# multi-pcb-analog.net
KiCad netlist of a schematic drawn in EAGLE
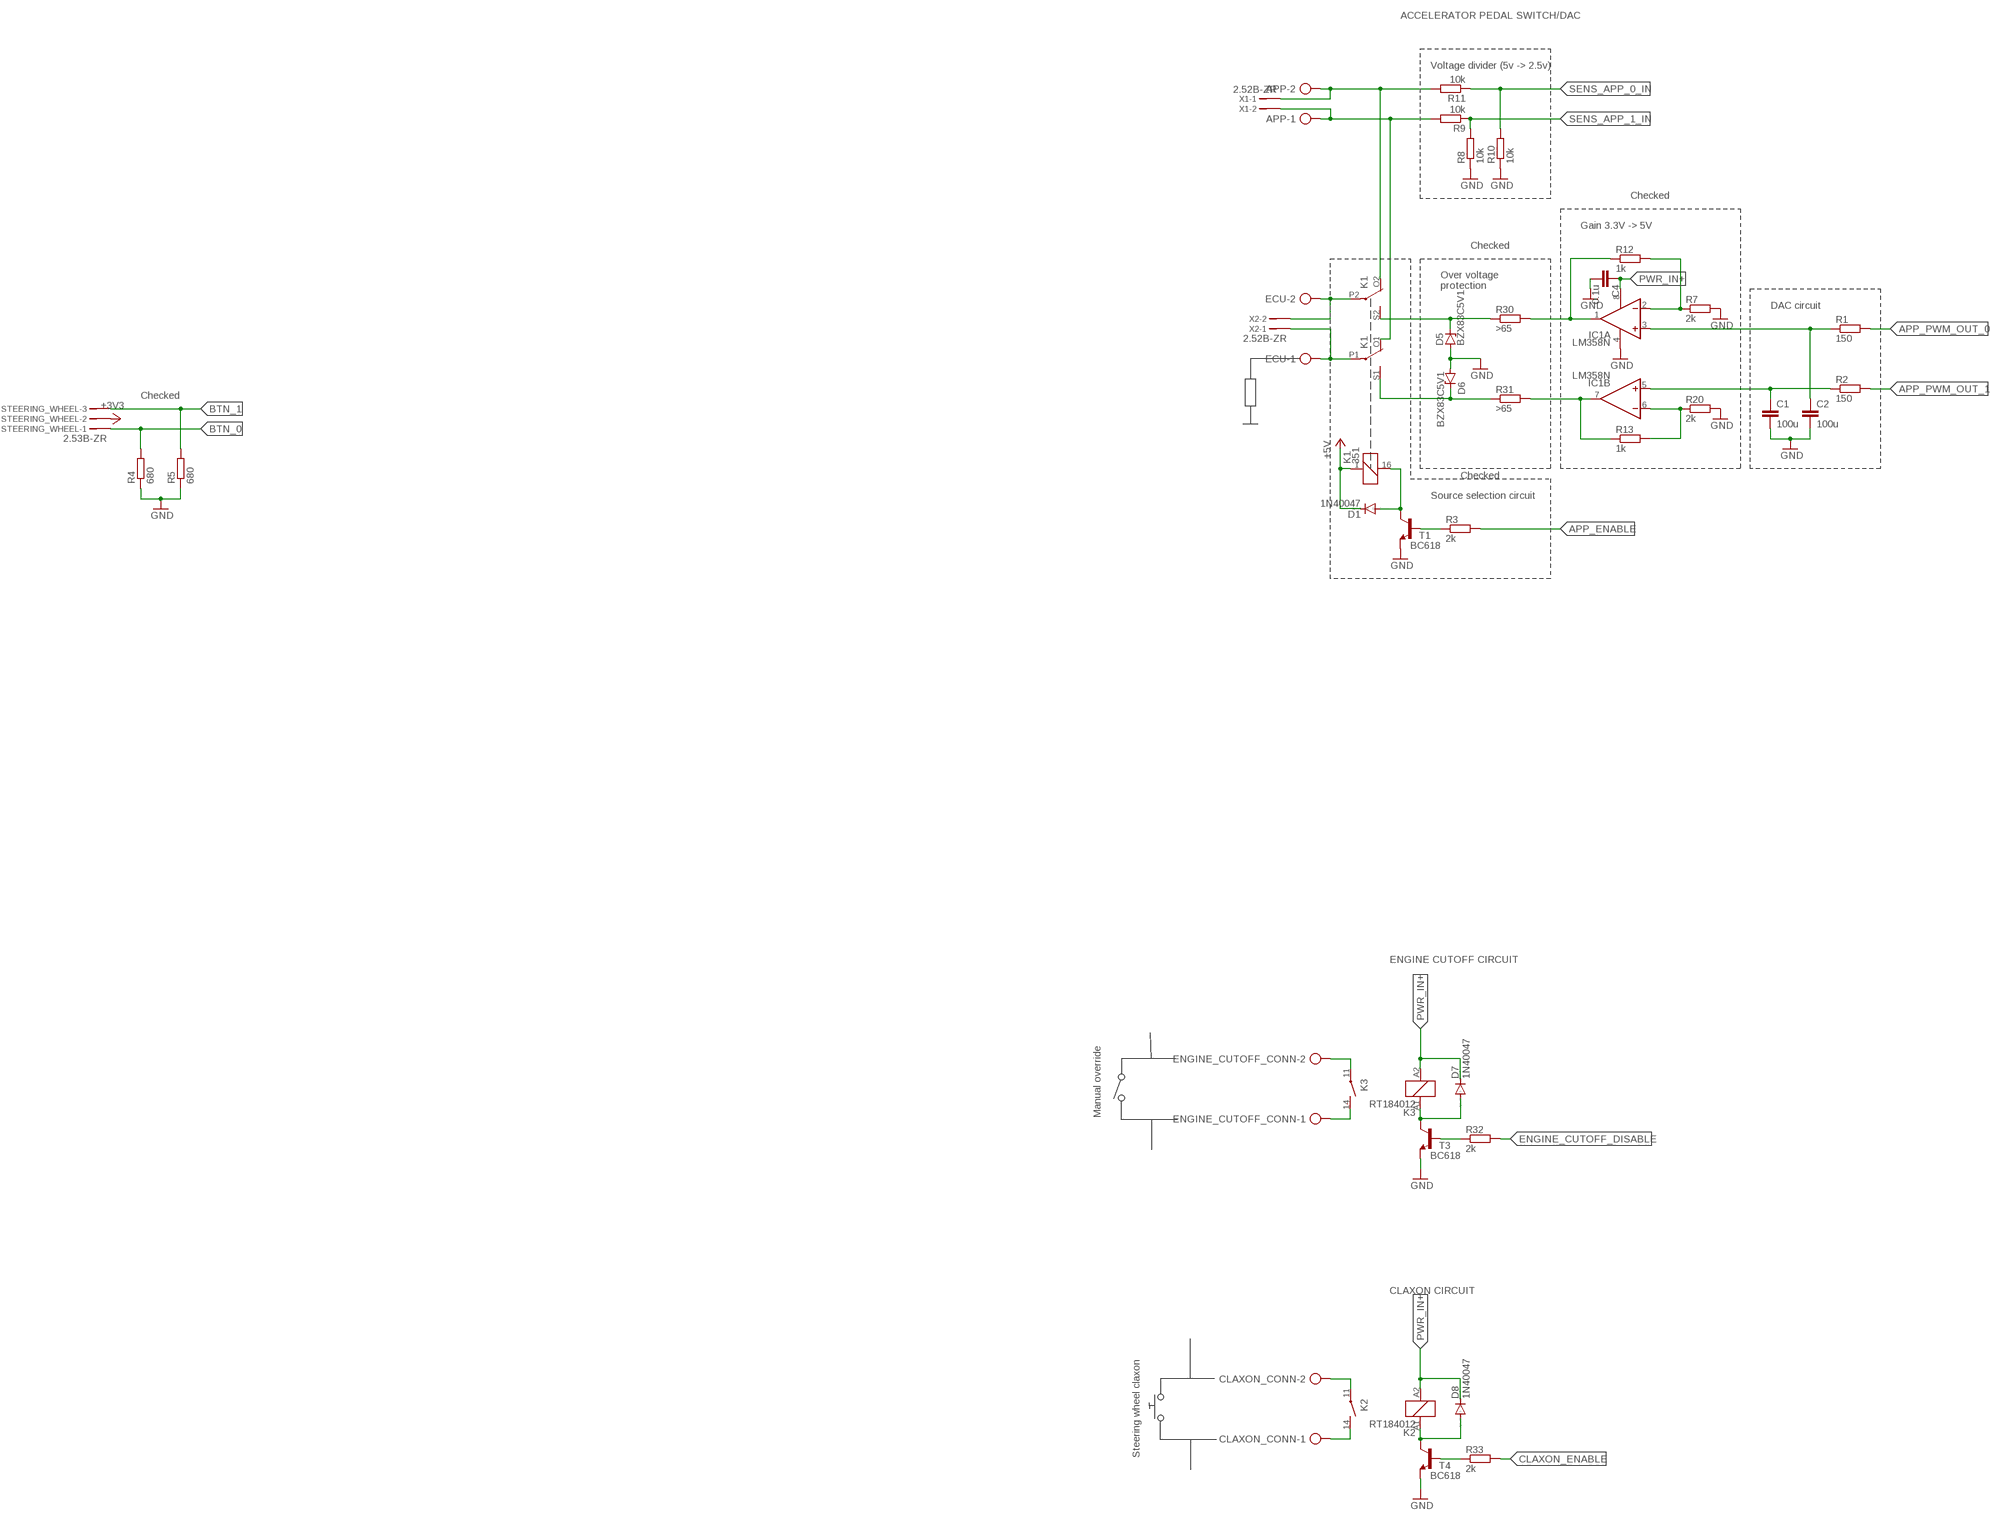
[diagram p0: schematic, sheet 1]

(export (version "E")
  (design (tool "Eeschema 10.0.6"))
  (components
    (comp (ref "APP")
      (value "AK300/2")
      (footprint "eagle-import:AK300_2")
      (libsource (lib "eagle-import") (part "AK300/2"))
    )
    (comp (ref "C1")
      (value "100u")
      (footprint "eagle-import:C025-050X050")
      (libsource (lib "eagle-import") (part "C-EU025-050X050"))
    )
    (comp (ref "C2")
      (value "100u")
      (footprint "eagle-import:C025-050X050")
      (libsource (lib "eagle-import") (part "C-EU025-050X050"))
    )
    (comp (ref "C4")
      (value "0.1u")
      (footprint "eagle-import:C025-050X050")
      (libsource (lib "eagle-import") (part "C-EU025-050X050"))
    )
    (comp (ref "CLAXON_CONN")
      (value "AK300/2")
      (footprint "eagle-import:AK300_2")
      (libsource (lib "eagle-import") (part "AK300/2"))
    )
    (comp (ref "D1")
      (value "1N40047")
      (footprint "eagle-import:DO41-7.6")
      (libsource (lib "eagle-import") (part "1N40047"))
    )
    (comp (ref "D5")
      (value "BZX83C5V1")
      (footprint "eagle-import:DO41Z7.6")
      (libsource (lib "eagle-import") (part "BZX857"))
    )
    (comp (ref "D6")
      (value "BZX83C5V1")
      (footprint "eagle-import:DO41Z7.6")
      (libsource (lib "eagle-import") (part "BZX857"))
    )
    (comp (ref "D7")
      (value "1N40047")
      (footprint "eagle-import:DO41-7.6")
      (libsource (lib "eagle-import") (part "1N40047"))
    )
    (comp (ref "D8")
      (value "1N40047")
      (footprint "eagle-import:DO41-7.6")
      (libsource (lib "eagle-import") (part "1N40047"))
    )
    (comp (ref "ECU")
      (value "AK300/2")
      (footprint "eagle-import:AK300_2")
      (libsource (lib "eagle-import") (part "AK300/2"))
    )
    (comp (ref "ENGINE_CUTOFF_CONN")
      (value "AK300/2")
      (footprint "eagle-import:AK300_2")
      (libsource (lib "eagle-import") (part "AK300/2"))
    )
    (comp (ref "IC1")
      (value "LM358N")
      (footprint "eagle-import:DIL08")
      (libsource (lib "eagle-import") (part "LM358N"))
    )
    (comp (ref "K1")
      (value "351")
      (footprint "eagle-import:351")
      (libsource (lib "eagle-import") (part "351"))
    )
    (comp (ref "K2")
      (value "RT184012")
      (footprint "eagle-import:RT-N_O12A3.5")
      (fields (field (name "MF") "TYCO ELECTRONICS"))
      (libsource (lib "eagle-import") (part "RT?184012"))
    )
    (comp (ref "K3")
      (value "RT184012")
      (footprint "eagle-import:RT-N_O12A3.5")
      (fields (field (name "MF") "TYCO ELECTRONICS"))
      (libsource (lib "eagle-import") (part "RT?184012"))
    )
    (comp (ref "R1")
      (value "150")
      (footprint "eagle-import:0309_10")
      (libsource (lib "eagle-import") (part "R-EU_0309/10"))
    )
    (comp (ref "R2")
      (value "150")
      (footprint "eagle-import:0309_10")
      (libsource (lib "eagle-import") (part "R-EU_0309/10"))
    )
    (comp (ref "R3")
      (value "2k")
      (footprint "eagle-import:0207_7")
      (libsource (lib "eagle-import") (part "R-EU_0207/7"))
    )
    (comp (ref "R4")
      (value "680")
      (footprint "eagle-import:0207_7")
      (libsource (lib "eagle-import") (part "R-EU_0207/7"))
    )
    (comp (ref "R5")
      (value "680")
      (footprint "eagle-import:0207_7")
      (libsource (lib "eagle-import") (part "R-EU_0207/7"))
    )
    (comp (ref "R7")
      (value "2k")
      (footprint "eagle-import:0207_7")
      (libsource (lib "eagle-import") (part "R-EU_0207/7"))
    )
    (comp (ref "R8")
      (value "10k")
      (footprint "eagle-import:0207_7")
      (libsource (lib "eagle-import") (part "R-EU_0207/7"))
    )
    (comp (ref "R9")
      (value "10k")
      (footprint "eagle-import:0309_10")
      (libsource (lib "eagle-import") (part "R-EU_0309/10"))
    )
    (comp (ref "R10")
      (value "10k")
      (footprint "eagle-import:0207_7")
      (libsource (lib "eagle-import") (part "R-EU_0207/7"))
    )
    (comp (ref "R11")
      (value "10k")
      (footprint "eagle-import:0309_10")
      (libsource (lib "eagle-import") (part "R-EU_0309/10"))
    )
    (comp (ref "R12")
      (value "1k")
      (footprint "eagle-import:0207_7")
      (libsource (lib "eagle-import") (part "R-EU_0207/7"))
    )
    (comp (ref "R13")
      (value "1k")
      (footprint "eagle-import:0207_7")
      (libsource (lib "eagle-import") (part "R-EU_0207/7"))
    )
    (comp (ref "R20")
      (value "2k")
      (footprint "eagle-import:0207_7")
      (libsource (lib "eagle-import") (part "R-EU_0207/7"))
    )
    (comp (ref "R30")
      (value ">65")
      (footprint "eagle-import:0207_7")
      (libsource (lib "eagle-import") (part "R-EU_0207/7"))
    )
    (comp (ref "R31")
      (value ">65")
      (footprint "eagle-import:0207_7")
      (libsource (lib "eagle-import") (part "R-EU_0207/7"))
    )
    (comp (ref "R32")
      (value "2k")
      (footprint "eagle-import:0309_10")
      (libsource (lib "eagle-import") (part "R-EU_0309/10"))
    )
    (comp (ref "R33")
      (value "2k")
      (footprint "eagle-import:0309_10")
      (libsource (lib "eagle-import") (part "R-EU_0309/10"))
    )
    (comp (ref "STEERING_WHEEL")
      (value "2.53B-ZR")
      (footprint "eagle-import:B3B-ZR2.5")
      (libsource (lib "eagle-import") (part "?3B-ZR2.5"))
    )
    (comp (ref "T1")
      (value "BC618")
      (footprint "eagle-import:TO92-EBC")
      (libsource (lib "eagle-import") (part "BC618"))
    )
    (comp (ref "T3")
      (value "BC618")
      (footprint "eagle-import:TO92-EBC")
      (libsource (lib "eagle-import") (part "BC618"))
    )
    (comp (ref "T4")
      (value "BC618")
      (footprint "eagle-import:TO92-EBC")
      (libsource (lib "eagle-import") (part "BC618"))
    )
    (comp (ref "X1")
      (value "2.52B-ZR")
      (footprint "eagle-import:B2B-ZR2.5")
      (libsource (lib "eagle-import") (part "?2B-ZR2.5"))
    )
    (comp (ref "X2")
      (value "2.52B-ZR")
      (footprint "eagle-import:B2B-ZR2.5")
      (libsource (lib "eagle-import") (part "?2B-ZR2.5"))
    )
  )
  (nets
    (net (code "1") (name "+3V3") (class "Default")
      (node (ref "STEERING_WHEEL") (pin "2") (pinfunction "1_2") (pintype "passive"))
    )
    (net (code "2") (name "+5V") (class "Default")
      (node (ref "D1") (pin "C") (pinfunction "C_C") (pintype "passive"))
      (node (ref "K1") (pin "1") (pinfunction "1_1") (pintype "passive"))
    )
    (net (code "3") (name "APP_ENABLE") (class "Default")
      (node (ref "R3") (pin "2") (pinfunction "2_2") (pintype "passive"))
    )
    (net (code "4") (name "APP_PWM_OUT_0") (class "Default")
      (node (ref "R1") (pin "2") (pinfunction "2_2") (pintype "passive"))
    )
    (net (code "5") (name "APP_PWM_OUT_1") (class "Default")
      (node (ref "R2") (pin "2") (pinfunction "2_2") (pintype "passive"))
    )
    (net (code "6") (name "BTN_0") (class "Default")
      (node (ref "R4") (pin "2") (pinfunction "2_2") (pintype "passive"))
      (node (ref "STEERING_WHEEL") (pin "1") (pinfunction "1_1") (pintype "passive"))
    )
    (net (code "7") (name "BTN_1") (class "Default")
      (node (ref "R5") (pin "2") (pinfunction "2_2") (pintype "passive"))
      (node (ref "STEERING_WHEEL") (pin "3") (pinfunction "1_3") (pintype "passive"))
    )
    (net (code "8") (name "CLAXON_ENABLE") (class "Default")
      (node (ref "R33") (pin "2") (pinfunction "2_2") (pintype "passive"))
    )
    (net (code "9") (name "ENGINE_CUTOFF_DISABLE") (class "Default")
      (node (ref "R32") (pin "2") (pinfunction "2_2") (pintype "passive"))
    )
    (net (code "10") (name "GND") (class "Default")
      (node (ref "C1") (pin "2") (pinfunction "2_2") (pintype "passive"))
      (node (ref "C2") (pin "2") (pinfunction "2_2") (pintype "passive"))
      (node (ref "C4") (pin "2") (pinfunction "2_2") (pintype "passive"))
      (node (ref "D5") (pin "A") (pinfunction "A_A") (pintype "passive"))
      (node (ref "D6") (pin "A") (pinfunction "A_A") (pintype "passive"))
      (node (ref "IC1") (pin "4") (pinfunction "V-_4") (pintype "power_in"))
      (node (ref "R10") (pin "1") (pinfunction "1_1") (pintype "passive"))
      (node (ref "R20") (pin "2") (pinfunction "2_2") (pintype "passive"))
      (node (ref "R4") (pin "1") (pinfunction "1_1") (pintype "passive"))
      (node (ref "R5") (pin "1") (pinfunction "1_1") (pintype "passive"))
      (node (ref "R7") (pin "2") (pinfunction "2_2") (pintype "passive"))
      (node (ref "R8") (pin "1") (pinfunction "1_1") (pintype "passive"))
      (node (ref "T1") (pin "E") (pinfunction "E_E") (pintype "passive"))
      (node (ref "T3") (pin "E") (pinfunction "E_E") (pintype "passive"))
      (node (ref "T4") (pin "E") (pinfunction "E_E") (pintype "passive"))
    )
    (net (code "11") (name "Net-(APPA-KL)") (class "Default")
      (node (ref "APP") (pin "1") (pinfunction "KL_1") (pintype "passive"))
      (node (ref "K1") (pin "O1") (pinfunction "O_O1") (pintype "passive"))
      (node (ref "R9") (pin "2") (pinfunction "2_2") (pintype "passive"))
      (node (ref "X1") (pin "2") (pinfunction "1_2") (pintype "passive"))
    )
    (net (code "12") (name "Net-(APPB-KL)") (class "Default")
      (node (ref "APP") (pin "2") (pinfunction "KL_2") (pintype "passive"))
      (node (ref "K1") (pin "O2") (pinfunction "O_O2") (pintype "passive"))
      (node (ref "R11") (pin "2") (pinfunction "2_2") (pintype "passive"))
      (node (ref "X1") (pin "1") (pinfunction "1_1") (pintype "passive"))
    )
    (net (code "13") (name "Net-(CLAXON_CONNA-KL)") (class "Default")
      (node (ref "CLAXON_CONN") (pin "1") (pinfunction "KL_1") (pintype "passive"))
      (node (ref "K2") (pin "14") (pinfunction "S_14") (pintype "passive"))
    )
    (net (code "14") (name "Net-(CLAXON_CONNB-KL)") (class "Default")
      (node (ref "CLAXON_CONN") (pin "2") (pinfunction "KL_2") (pintype "passive"))
      (node (ref "K2") (pin "11") (pinfunction "P_11") (pintype "passive"))
    )
    (net (code "15") (name "Net-(ECUA-KL)") (class "Default")
      (node (ref "ECU") (pin "1") (pinfunction "KL_1") (pintype "passive"))
      (node (ref "K1") (pin "P1") (pinfunction "P_P1") (pintype "passive"))
      (node (ref "X2") (pin "1") (pinfunction "1_1") (pintype "passive"))
    )
    (net (code "16") (name "Net-(ECUB-KL)") (class "Default")
      (node (ref "ECU") (pin "2") (pinfunction "KL_2") (pintype "passive"))
      (node (ref "K1") (pin "P2") (pinfunction "P_P2") (pintype "passive"))
      (node (ref "X2") (pin "2") (pinfunction "1_2") (pintype "passive"))
    )
    (net (code "17") (name "Net-(ENGINE_CUTOFF_CONNA-KL)") (class "Default")
      (node (ref "ENGINE_CUTOFF_CONN") (pin "1") (pinfunction "KL_1") (pintype "passive"))
      (node (ref "K3") (pin "14") (pinfunction "S_14") (pintype "passive"))
    )
    (net (code "18") (name "Net-(ENGINE_CUTOFF_CONNB-KL)") (class "Default")
      (node (ref "ENGINE_CUTOFF_CONN") (pin "2") (pinfunction "KL_2") (pintype "passive"))
      (node (ref "K3") (pin "11") (pinfunction "P_11") (pintype "passive"))
    )
    (net (code "19") (name "Net-(IC1A-+IN)") (class "Default")
      (node (ref "C2") (pin "1") (pinfunction "1_1") (pintype "passive"))
      (node (ref "IC1") (pin "3") (pinfunction "+IN_3") (pintype "input"))
      (node (ref "R1") (pin "1") (pinfunction "1_1") (pintype "passive"))
    )
    (net (code "20") (name "Net-(IC1A--IN)") (class "Default")
      (node (ref "IC1") (pin "2") (pinfunction "-IN_2") (pintype "input"))
      (node (ref "R12") (pin "2") (pinfunction "2_2") (pintype "passive"))
      (node (ref "R7") (pin "1") (pinfunction "1_1") (pintype "passive"))
    )
    (net (code "21") (name "Net-(IC1A-OUT)") (class "Default")
      (node (ref "IC1") (pin "1") (pinfunction "OUT_1") (pintype "output"))
      (node (ref "R12") (pin "1") (pinfunction "1_1") (pintype "passive"))
      (node (ref "R30") (pin "2") (pinfunction "2_2") (pintype "passive"))
    )
    (net (code "22") (name "Net-(IC1B-+IN)") (class "Default")
      (node (ref "C1") (pin "1") (pinfunction "1_1") (pintype "passive"))
      (node (ref "IC1") (pin "5") (pinfunction "+IN_5") (pintype "input"))
      (node (ref "R2") (pin "1") (pinfunction "1_1") (pintype "passive"))
    )
    (net (code "23") (name "Net-(IC1B--IN)") (class "Default")
      (node (ref "IC1") (pin "6") (pinfunction "-IN_6") (pintype "input"))
      (node (ref "R13") (pin "2") (pinfunction "2_2") (pintype "passive"))
      (node (ref "R20") (pin "1") (pinfunction "1_1") (pintype "passive"))
    )
    (net (code "24") (name "Net-(IC1B-OUT)") (class "Default")
      (node (ref "IC1") (pin "7") (pinfunction "OUT_7") (pintype "output"))
      (node (ref "R13") (pin "1") (pinfunction "1_1") (pintype "passive"))
      (node (ref "R31") (pin "2") (pinfunction "2_2") (pintype "passive"))
    )
    (net (code "25") (name "Net-(K1A-2)") (class "Default")
      (node (ref "D1") (pin "A") (pinfunction "A_A") (pintype "passive"))
      (node (ref "K1") (pin "16") (pinfunction "2_16") (pintype "passive"))
      (node (ref "T1") (pin "C") (pinfunction "C_C") (pintype "passive"))
    )
    (net (code "26") (name "Net-(K1B-S)") (class "Default")
      (node (ref "D6") (pin "C") (pinfunction "C_C") (pintype "passive"))
      (node (ref "K1") (pin "S1") (pinfunction "S_S1") (pintype "passive"))
      (node (ref "R31") (pin "1") (pinfunction "1_1") (pintype "passive"))
    )
    (net (code "27") (name "Net-(K1C-S)") (class "Default")
      (node (ref "D5") (pin "C") (pinfunction "C_C") (pintype "passive"))
      (node (ref "K1") (pin "S2") (pinfunction "S_S2") (pintype "passive"))
      (node (ref "R30") (pin "1") (pinfunction "1_1") (pintype "passive"))
    )
    (net (code "28") (name "Net-(K2A-1)") (class "Default")
      (node (ref "D8") (pin "A") (pinfunction "A_A") (pintype "passive"))
      (node (ref "K2") (pin "A1") (pinfunction "1_A1") (pintype "passive"))
      (node (ref "T4") (pin "C") (pinfunction "C_C") (pintype "passive"))
    )
    (net (code "29") (name "Net-(K3A-1)") (class "Default")
      (node (ref "D7") (pin "A") (pinfunction "A_A") (pintype "passive"))
      (node (ref "K3") (pin "A1") (pinfunction "1_A1") (pintype "passive"))
      (node (ref "T3") (pin "C") (pinfunction "C_C") (pintype "passive"))
    )
    (net (code "30") (name "Net-(R3-Pad1)") (class "Default")
      (node (ref "R3") (pin "1") (pinfunction "1_1") (pintype "passive"))
      (node (ref "T1") (pin "B") (pinfunction "B_B") (pintype "passive"))
    )
    (net (code "31") (name "Net-(R32-Pad1)") (class "Default")
      (node (ref "R32") (pin "1") (pinfunction "1_1") (pintype "passive"))
      (node (ref "T3") (pin "B") (pinfunction "B_B") (pintype "passive"))
    )
    (net (code "32") (name "Net-(R33-Pad1)") (class "Default")
      (node (ref "R33") (pin "1") (pinfunction "1_1") (pintype "passive"))
      (node (ref "T4") (pin "B") (pinfunction "B_B") (pintype "passive"))
    )
    (net (code "33") (name "PWR_IN+") (class "Default")
      (node (ref "C4") (pin "1") (pinfunction "1_1") (pintype "passive"))
      (node (ref "D7") (pin "C") (pinfunction "C_C") (pintype "passive"))
      (node (ref "D8") (pin "C") (pinfunction "C_C") (pintype "passive"))
      (node (ref "IC1") (pin "8") (pinfunction "V+_8") (pintype "power_in"))
      (node (ref "K2") (pin "A2") (pinfunction "2_A2") (pintype "passive"))
      (node (ref "K3") (pin "A2") (pinfunction "2_A2") (pintype "passive"))
    )
    (net (code "34") (name "SENS_APP_0_IN") (class "Default")
      (node (ref "R10") (pin "2") (pinfunction "2_2") (pintype "passive"))
      (node (ref "R11") (pin "1") (pinfunction "1_1") (pintype "passive"))
    )
    (net (code "35") (name "SENS_APP_1_IN") (class "Default")
      (node (ref "R8") (pin "2") (pinfunction "2_2") (pintype "passive"))
      (node (ref "R9") (pin "1") (pinfunction "1_1") (pintype "passive"))
    )
  )
)
